# picoAvaR4-routed.net
KiCad netlist of a schematic drawn in EAGLE
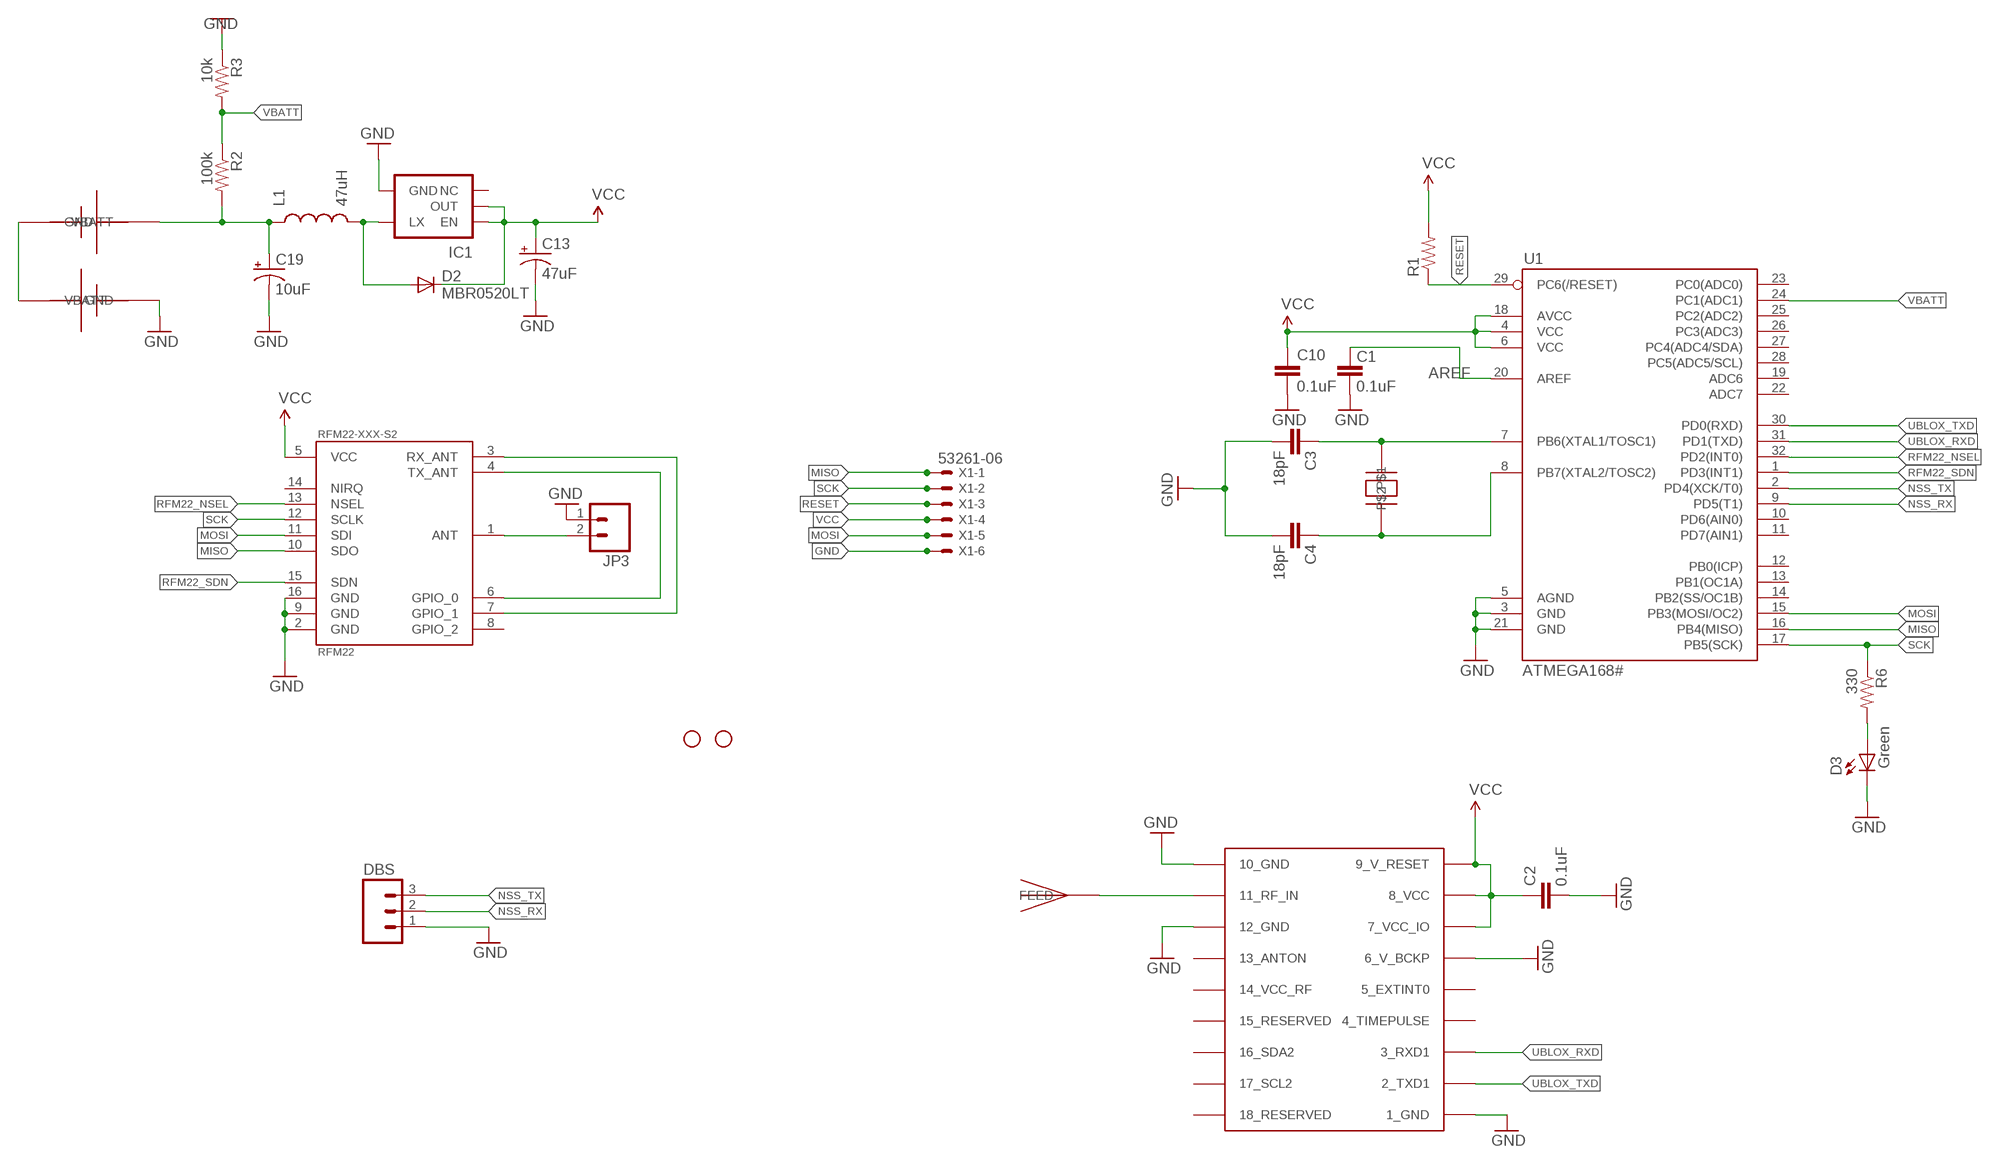
[diagram p0: schematic, sheet 1]

(export (version "E")
  (design (tool "Eeschema 10.0.6"))
  (components
    (comp (ref "C1")
      (value "0.1uF")
      (footprint "eagle-import:0402-CAP")
      (libsource (lib "eagle-import") (part "CAP0402-CAP"))
    )
    (comp (ref "C2")
      (value "0.1uF")
      (footprint "eagle-import:0402-CAP")
      (libsource (lib "eagle-import") (part "CAP0402-CAP"))
    )
    (comp (ref "C3")
      (value "18pF")
      (footprint "eagle-import:0402-CAP")
      (libsource (lib "eagle-import") (part "CAP0402-CAP"))
    )
    (comp (ref "C4")
      (value "18pF")
      (footprint "eagle-import:0402-CAP")
      (libsource (lib "eagle-import") (part "CAP0402-CAP"))
    )
    (comp (ref "C10")
      (value "0.1uF")
      (footprint "eagle-import:0402-CAP")
      (libsource (lib "eagle-import") (part "CAP0402-CAP"))
    )
    (comp (ref "C13")
      (value "47uF")
      (footprint "eagle-import:EIA3216")
      (libsource (lib "eagle-import") (part "CAP_POL1206"))
    )
    (comp (ref "C19")
      (value "10uF")
      (footprint "eagle-import:EIA3216")
      (libsource (lib "eagle-import") (part "CAP_POL1206"))
    )
    (comp (ref "D2")
      (value "MBR0520LT")
      (footprint "eagle-import:SOD123")
      (libsource (lib "eagle-import") (part "MBR0520LT"))
    )
    (comp (ref "D3")
      (value "Green")
      (footprint "eagle-import:LED-0603")
      (libsource (lib "eagle-import") (part "LED0603"))
    )
    (comp (ref "DBS")
      (value "M03PTH")
      (footprint "eagle-import:1X03")
      (libsource (lib "eagle-import") (part "M03PTH"))
    )
    (comp (ref "IC1")
      (value "V_REG_NCP1400SOT23-5")
      (footprint "eagle-import:SOT23-5")
      (libsource (lib "eagle-import") (part "V_REG_NCP1400SOT23-5"))
    )
    (comp (ref "JP1")
      (value "STAND-OFF")
      (footprint "eagle-import:STAND-OFF")
      (libsource (lib "eagle-import") (part "STAND-OFF"))
    )
    (comp (ref "JP2")
      (value "STAND-OFF")
      (footprint "eagle-import:STAND-OFF")
      (libsource (lib "eagle-import") (part "STAND-OFF"))
    )
    (comp (ref "JP3")
      (value "M02PTH")
      (footprint "eagle-import:1X02")
      (libsource (lib "eagle-import") (part "M02PTH"))
    )
    (comp (ref "L1")
      (value "47uH")
      (footprint "eagle-import:1210")
      (libsource (lib "eagle-import") (part "INDUCTOR1210"))
    )
    (comp (ref "R1")
      (value "RESISTOR0402-RES")
      (footprint "eagle-import:0402-RES")
      (libsource (lib "eagle-import") (part "RESISTOR0402-RES"))
    )
    (comp (ref "R2")
      (value "100k")
      (footprint "eagle-import:0402-RES")
      (libsource (lib "eagle-import") (part "RESISTOR0402-RES"))
    )
    (comp (ref "R3")
      (value "10k")
      (footprint "eagle-import:0402-RES")
      (libsource (lib "eagle-import") (part "RESISTOR0402-RES"))
    )
    (comp (ref "R6")
      (value "330")
      (footprint "eagle-import:0402-RES")
      (libsource (lib "eagle-import") (part "RESISTOR0402-RES"))
    )
    (comp (ref "RFM22-XXX-S2")
      (value "RFM22")
      (footprint "eagle-import:RFM22-XXX-S2")
      (libsource (lib "eagle-import") (part "RFM22"))
    )
    (comp (ref "U$1")
      (value "UBLOX_MAX-6")
      (footprint "eagle-import:UBLOX_MAX-6")
      (libsource (lib "eagle-import") (part "UBLOX_MAX-6"))
    )
    (comp (ref "U$2")
      (value "ABRACON_ABM3_CRYSTAL")
      (footprint "eagle-import:ABRACON_ABM3_CRYSTAL")
      (libsource (lib "eagle-import") (part "ABRACON_ABM3_CRYSTAL"))
    )
    (comp (ref "U$3")
      (value "JTI_ANTENNA-1575AT43A40")
      (footprint "eagle-import:JTI_ANTENNA-1575AT43A40")
      (libsource (lib "eagle-import") (part "JTI_ANTENNA-1575AT43A40"))
    )
    (comp (ref "U$4")
      (value "KEYSTONE-82-AAA-BATTERY-HOLDER")
      (footprint "eagle-import:KEYSTONE-82-AAA-BATTERY")
      (libsource (lib "eagle-import") (part "KEYSTONE-82-AAA-BATTERY-HOLDER"))
    )
    (comp (ref "U$5")
      (value "KEYSTONE-82-AAA-BATTERY-HOLDER")
      (footprint "eagle-import:KEYSTONE-82-AAA-BATTERY")
      (libsource (lib "eagle-import") (part "KEYSTONE-82-AAA-BATTERY-HOLDER"))
    )
    (comp (ref "U1")
      (value "ATMEGA168#")
      (footprint "eagle-import:TQFP32-08")
      (libsource (lib "eagle-import") (part "ATMEGA168"))
    )
    (comp (ref "X1")
      (value "53261-06")
      (footprint "eagle-import:53261-06")
      (libsource (lib "eagle-import") (part "53?-06261"))
    )
  )
  (nets
    (net (code "1") (name "/AREF") (class "Default")
      (node (ref "C1") (pin "2") (pinfunction "2_2") (pintype "passive"))
      (node (ref "U1") (pin "20") (pinfunction "AREF_20") (pintype "bidirectional"))
    )
    (net (code "2") (name "GND") (class "Default")
      (node (ref "C1") (pin "1") (pinfunction "1_1") (pintype "passive"))
      (node (ref "C10") (pin "2") (pinfunction "2_2") (pintype "passive"))
      (node (ref "C13") (pin "C") (pinfunction "-_C") (pintype "passive"))
      (node (ref "C19") (pin "C") (pinfunction "-_C") (pintype "passive"))
      (node (ref "C2") (pin "2") (pinfunction "2_2") (pintype "passive"))
      (node (ref "C3") (pin "2") (pinfunction "2_2") (pintype "passive"))
      (node (ref "C4") (pin "2") (pinfunction "2_2") (pintype "passive"))
      (node (ref "D3") (pin "C") (pinfunction "C_C") (pintype "passive"))
      (node (ref "DBS") (pin "1") (pinfunction "1_1") (pintype "passive"))
      (node (ref "IC1") (pin "4") (pinfunction "GND_4") (pintype "input"))
      (node (ref "JP3") (pin "1") (pinfunction "1_1") (pintype "passive"))
      (node (ref "R3") (pin "1") (pinfunction "1_1") (pintype "passive"))
      (node (ref "RFM22-XXX-S2") (pin "16") (pinfunction "GND_16") (pintype "power_in"))
      (node (ref "RFM22-XXX-S2") (pin "2") (pinfunction "GND_2") (pintype "power_in"))
      (node (ref "RFM22-XXX-S2") (pin "9") (pinfunction "GND_9") (pintype "power_in"))
      (node (ref "U$1") (pin "10_GND") (pinfunction "10_GND_10_GND") (pintype "bidirectional"))
      (node (ref "U$1") (pin "12_GND") (pinfunction "12_GND_12_GND") (pintype "bidirectional"))
      (node (ref "U$1") (pin "1_GND") (pinfunction "1_GND_1_GND") (pintype "bidirectional"))
      (node (ref "U$1") (pin "6_V_BCKP") (pinfunction "6_V_BCKP_6_V_BCKP") (pintype "bidirectional"))
      (node (ref "U$5") (pin "GND") (pinfunction "GND_GND") (pintype "bidirectional"))
      (node (ref "U$5") (pin "GND2") (pinfunction "GND_GND2") (pintype "bidirectional"))
      (node (ref "U1") (pin "21") (pinfunction "GND_21") (pintype "bidirectional"))
      (node (ref "U1") (pin "3") (pinfunction "GND_3") (pintype "bidirectional"))
      (node (ref "U1") (pin "5") (pinfunction "AGND_5") (pintype "bidirectional"))
      (node (ref "X1") (pin "6") (pinfunction "S_6") (pintype "passive"))
    )
    (net (code "3") (name "MISO") (class "Default")
      (node (ref "RFM22-XXX-S2") (pin "10") (pinfunction "SDO_10") (pintype "output"))
      (node (ref "U1") (pin "16") (pinfunction "PB4(MISO)_16") (pintype "bidirectional"))
      (node (ref "X1") (pin "1") (pinfunction "S_1") (pintype "passive"))
    )
    (net (code "4") (name "MOSI") (class "Default")
      (node (ref "RFM22-XXX-S2") (pin "11") (pinfunction "SDI_11") (pintype "input"))
      (node (ref "U1") (pin "15") (pinfunction "PB3(MOSI/OC2)_15") (pintype "bidirectional"))
      (node (ref "X1") (pin "5") (pinfunction "S_5") (pintype "passive"))
    )
    (net (code "5") (name "NSS_RX") (class "Default")
      (node (ref "DBS") (pin "2") (pinfunction "2_2") (pintype "passive"))
      (node (ref "U1") (pin "9") (pinfunction "PD5(T1)_9") (pintype "bidirectional"))
    )
    (net (code "6") (name "NSS_TX") (class "Default")
      (node (ref "DBS") (pin "3") (pinfunction "3_3") (pintype "passive"))
      (node (ref "U1") (pin "2") (pinfunction "PD4(XCK/T0)_2") (pintype "bidirectional"))
    )
    (net (code "7") (name "Net-(C19-+)") (class "Default")
      (node (ref "C19") (pin "A") (pinfunction "+_A") (pintype "passive"))
      (node (ref "L1") (pin "1") (pinfunction "1_1") (pintype "passive"))
      (node (ref "R2") (pin "2") (pinfunction "2_2") (pintype "passive"))
      (node (ref "U$4") (pin "VBATT") (pinfunction "VBATT_VBATT") (pintype "bidirectional"))
      (node (ref "U$4") (pin "VBATT1") (pinfunction "VBATT_VBATT1") (pintype "bidirectional"))
    )
    (net (code "8") (name "Net-(D3-PadA)") (class "Default")
      (node (ref "D3") (pin "A") (pinfunction "A_A") (pintype "passive"))
      (node (ref "R6") (pin "2") (pinfunction "2_2") (pintype "passive"))
    )
    (net (code "9") (name "Net-(IC1-LX)") (class "Default")
      (node (ref "D2") (pin "A") (pinfunction "A_A") (pintype "passive"))
      (node (ref "IC1") (pin "5") (pinfunction "LX_5") (pintype "input"))
      (node (ref "L1") (pin "2") (pinfunction "2_2") (pintype "passive"))
    )
    (net (code "10") (name "Net-(RFM22-XXX-S2-ANT)") (class "Default")
      (node (ref "JP3") (pin "2") (pinfunction "2_2") (pintype "passive"))
      (node (ref "RFM22-XXX-S2") (pin "1") (pinfunction "ANT_1") (pintype "bidirectional"))
    )
    (net (code "11") (name "Net-(RFM22-XXX-S2-GPIO_0)") (class "Default")
      (node (ref "RFM22-XXX-S2") (pin "4") (pinfunction "TX_ANT_4") (pintype "input"))
      (node (ref "RFM22-XXX-S2") (pin "6") (pinfunction "GPIO_0_6") (pintype "bidirectional"))
    )
    (net (code "12") (name "Net-(RFM22-XXX-S2-GPIO_1)") (class "Default")
      (node (ref "RFM22-XXX-S2") (pin "3") (pinfunction "RX_ANT_3") (pintype "input"))
      (node (ref "RFM22-XXX-S2") (pin "7") (pinfunction "GPIO_1_7") (pintype "bidirectional"))
    )
    (net (code "13") (name "Net-(U$1-Pad11_RF_IN)") (class "Default")
      (node (ref "U$1") (pin "11_RF_IN") (pinfunction "11_RF_IN_11_RF_IN") (pintype "bidirectional"))
      (node (ref "U$3") (pin "FEED") (pinfunction "FEED_FEED") (pintype "bidirectional"))
    )
    (net (code "14") (name "Net-(U$4-GND-PadGND2)") (class "Default")
      (node (ref "U$4") (pin "GND") (pinfunction "GND_GND") (pintype "bidirectional"))
      (node (ref "U$4") (pin "GND2") (pinfunction "GND_GND2") (pintype "bidirectional"))
      (node (ref "U$5") (pin "VBATT") (pinfunction "VBATT_VBATT") (pintype "bidirectional"))
      (node (ref "U$5") (pin "VBATT1") (pinfunction "VBATT_VBATT1") (pintype "bidirectional"))
    )
    (net (code "15") (name "Net-(U1-PB6(XTAL1{slash}TOSC1))") (class "Default")
      (node (ref "C3") (pin "1") (pinfunction "1_1") (pintype "passive"))
      (node (ref "U$2") (pin "P$2") (pinfunction "P$2_P$2") (pintype "bidirectional"))
      (node (ref "U1") (pin "7") (pinfunction "PB6(XTAL1/TOSC1)_7") (pintype "bidirectional"))
    )
    (net (code "16") (name "Net-(U1-PB7(XTAL2{slash}TOSC2))") (class "Default")
      (node (ref "C4") (pin "1") (pinfunction "1_1") (pintype "passive"))
      (node (ref "U$2") (pin "P$1") (pinfunction "P$1_P$1") (pintype "bidirectional"))
      (node (ref "U1") (pin "8") (pinfunction "PB7(XTAL2/TOSC2)_8") (pintype "bidirectional"))
    )
    (net (code "17") (name "RESET") (class "Default")
      (node (ref "R1") (pin "1") (pinfunction "1_1") (pintype "passive"))
      (node (ref "U1") (pin "29") (pinfunction "PC6(/RESET)_29") (pintype "bidirectional"))
      (node (ref "X1") (pin "3") (pinfunction "S_3") (pintype "passive"))
    )
    (net (code "18") (name "RFM22_NSEL") (class "Default")
      (node (ref "RFM22-XXX-S2") (pin "13") (pinfunction "NSEL_13") (pintype "input"))
      (node (ref "U1") (pin "32") (pinfunction "PD2(INT0)_32") (pintype "bidirectional"))
    )
    (net (code "19") (name "RFM22_SDN") (class "Default")
      (node (ref "RFM22-XXX-S2") (pin "15") (pinfunction "SDN_15") (pintype "input"))
      (node (ref "U1") (pin "1") (pinfunction "PD3(INT1)_1") (pintype "bidirectional"))
    )
    (net (code "20") (name "SCK") (class "Default")
      (node (ref "R6") (pin "1") (pinfunction "1_1") (pintype "passive"))
      (node (ref "RFM22-XXX-S2") (pin "12") (pinfunction "SCLK_12") (pintype "input"))
      (node (ref "U1") (pin "17") (pinfunction "PB5(SCK)_17") (pintype "bidirectional"))
      (node (ref "X1") (pin "2") (pinfunction "S_2") (pintype "passive"))
    )
    (net (code "21") (name "UBLOX_RXD") (class "Default")
      (node (ref "U$1") (pin "3_RXD1") (pinfunction "3_RXD1_3_RXD1") (pintype "bidirectional"))
      (node (ref "U1") (pin "31") (pinfunction "PD1(TXD)_31") (pintype "bidirectional"))
    )
    (net (code "22") (name "UBLOX_TXD") (class "Default")
      (node (ref "U$1") (pin "2_TXD1") (pinfunction "2_TXD1_2_TXD1") (pintype "bidirectional"))
      (node (ref "U1") (pin "30") (pinfunction "PD0(RXD)_30") (pintype "bidirectional"))
    )
    (net (code "23") (name "VBATT") (class "Default")
      (node (ref "R2") (pin "1") (pinfunction "1_1") (pintype "passive"))
      (node (ref "R3") (pin "2") (pinfunction "2_2") (pintype "passive"))
      (node (ref "U1") (pin "24") (pinfunction "PC1(ADC1)_24") (pintype "bidirectional"))
    )
    (net (code "24") (name "VCC") (class "Default")
      (node (ref "C10") (pin "1") (pinfunction "1_1") (pintype "passive"))
      (node (ref "C13") (pin "A") (pinfunction "+_A") (pintype "passive"))
      (node (ref "C2") (pin "1") (pinfunction "1_1") (pintype "passive"))
      (node (ref "D2") (pin "C") (pinfunction "C_C") (pintype "passive"))
      (node (ref "IC1") (pin "1") (pinfunction "EN_1") (pintype "input"))
      (node (ref "IC1") (pin "2") (pinfunction "OUT_2") (pintype "passive"))
      (node (ref "R1") (pin "2") (pinfunction "2_2") (pintype "passive"))
      (node (ref "RFM22-XXX-S2") (pin "5") (pinfunction "VCC_5") (pintype "bidirectional"))
      (node (ref "U$1") (pin "7_VCC_IO") (pinfunction "7_VCC_IO_7_VCC_IO") (pintype "bidirectional"))
      (node (ref "U$1") (pin "8_VCC") (pinfunction "8_VCC_8_VCC") (pintype "bidirectional"))
      (node (ref "U$1") (pin "9_V_RESET") (pinfunction "9_V_RESET_9_V_RESET") (pintype "bidirectional"))
      (node (ref "U1") (pin "18") (pinfunction "AVCC_18") (pintype "bidirectional"))
      (node (ref "U1") (pin "4") (pinfunction "VCC_4") (pintype "bidirectional"))
      (node (ref "U1") (pin "6") (pinfunction "VCC_6") (pintype "bidirectional"))
      (node (ref "X1") (pin "4") (pinfunction "S_4") (pintype "passive"))
    )
    (net (code "25") (name "unconnected-(IC1-NC-Pad3)") (class "Default")
      (node (ref "IC1") (pin "3") (pinfunction "NC_3") (pintype "input"))
    )
    (net (code "26") (name "unconnected-(RFM22-XXX-S2-GPIO_2-Pad8)") (class "Default")
      (node (ref "RFM22-XXX-S2") (pin "8") (pinfunction "GPIO_2_8") (pintype "bidirectional"))
    )
    (net (code "27") (name "unconnected-(RFM22-XXX-S2-NIRQ-Pad14)") (class "Default")
      (node (ref "RFM22-XXX-S2") (pin "14") (pinfunction "NIRQ_14") (pintype "output"))
    )
    (net (code "28") (name "unconnected-(U$1-Pad4_TIMEPULSE)") (class "Default")
      (node (ref "U$1") (pin "4_TIMEPULSE") (pinfunction "4_TIMEPULSE_4_TIMEPULSE") (pintype "bidirectional"))
    )
    (net (code "29") (name "unconnected-(U$1-Pad5_EXTINT0)") (class "Default")
      (node (ref "U$1") (pin "5_EXTINT0") (pinfunction "5_EXTINT0_5_EXTINT0") (pintype "bidirectional"))
    )
    (net (code "30") (name "unconnected-(U$1-Pad13_ANTON)") (class "Default")
      (node (ref "U$1") (pin "13_ANTON") (pinfunction "13_ANTON_13_ANTON") (pintype "bidirectional"))
    )
    (net (code "31") (name "unconnected-(U$1-Pad14_VCC_RF)") (class "Default")
      (node (ref "U$1") (pin "14_VCC_RF") (pinfunction "14_VCC_RF_14_VCC_RF") (pintype "bidirectional"))
    )
    (net (code "32") (name "unconnected-(U$1-Pad15_RESERVED)") (class "Default")
      (node (ref "U$1") (pin "15_RESERVED") (pinfunction "15_RESERVED_15_RESERVED") (pintype "bidirectional"))
    )
    (net (code "33") (name "unconnected-(U$1-Pad16_SDA2)") (class "Default")
      (node (ref "U$1") (pin "16_SDA2") (pinfunction "16_SDA2_16_SDA2") (pintype "bidirectional"))
    )
    (net (code "34") (name "unconnected-(U$1-Pad17_SCL2)") (class "Default")
      (node (ref "U$1") (pin "17_SCL2") (pinfunction "17_SCL2_17_SCL2") (pintype "bidirectional"))
    )
    (net (code "35") (name "unconnected-(U$1-Pad18_RESERVED)") (class "Default")
      (node (ref "U$1") (pin "18_RESERVED") (pinfunction "18_RESERVED_18_RESERVED") (pintype "bidirectional"))
    )
    (net (code "36") (name "unconnected-(U1-ADC6-Pad19)") (class "Default")
      (node (ref "U1") (pin "19") (pinfunction "ADC6_19") (pintype "bidirectional"))
    )
    (net (code "37") (name "unconnected-(U1-ADC7-Pad22)") (class "Default")
      (node (ref "U1") (pin "22") (pinfunction "ADC7_22") (pintype "bidirectional"))
    )
    (net (code "38") (name "unconnected-(U1-PB0(ICP)-Pad12)") (class "Default")
      (node (ref "U1") (pin "12") (pinfunction "PB0(ICP)_12") (pintype "bidirectional"))
    )
    (net (code "39") (name "unconnected-(U1-PB1(OC1A)-Pad13)") (class "Default")
      (node (ref "U1") (pin "13") (pinfunction "PB1(OC1A)_13") (pintype "bidirectional"))
    )
    (net (code "40") (name "unconnected-(U1-PB2(SS{slash}OC1B)-Pad14)") (class "Default")
      (node (ref "U1") (pin "14") (pinfunction "PB2(SS/OC1B)_14") (pintype "bidirectional"))
    )
    (net (code "41") (name "unconnected-(U1-PC0(ADC0)-Pad23)") (class "Default")
      (node (ref "U1") (pin "23") (pinfunction "PC0(ADC0)_23") (pintype "bidirectional"))
    )
    (net (code "42") (name "unconnected-(U1-PC2(ADC2)-Pad25)") (class "Default")
      (node (ref "U1") (pin "25") (pinfunction "PC2(ADC2)_25") (pintype "bidirectional"))
    )
    (net (code "43") (name "unconnected-(U1-PC3(ADC3)-Pad26)") (class "Default")
      (node (ref "U1") (pin "26") (pinfunction "PC3(ADC3)_26") (pintype "bidirectional"))
    )
    (net (code "44") (name "unconnected-(U1-PC4(ADC4{slash}SDA)-Pad27)") (class "Default")
      (node (ref "U1") (pin "27") (pinfunction "PC4(ADC4/SDA)_27") (pintype "bidirectional"))
    )
    (net (code "45") (name "unconnected-(U1-PC5(ADC5{slash}SCL)-Pad28)") (class "Default")
      (node (ref "U1") (pin "28") (pinfunction "PC5(ADC5/SCL)_28") (pintype "bidirectional"))
    )
    (net (code "46") (name "unconnected-(U1-PD6(AIN0)-Pad10)") (class "Default")
      (node (ref "U1") (pin "10") (pinfunction "PD6(AIN0)_10") (pintype "bidirectional"))
    )
    (net (code "47") (name "unconnected-(U1-PD7(AIN1)-Pad11)") (class "Default")
      (node (ref "U1") (pin "11") (pinfunction "PD7(AIN1)_11") (pintype "bidirectional"))
    )
  )
)
